# Eeprom.net
KiCad netlist of a schematic drawn in Altium Designer
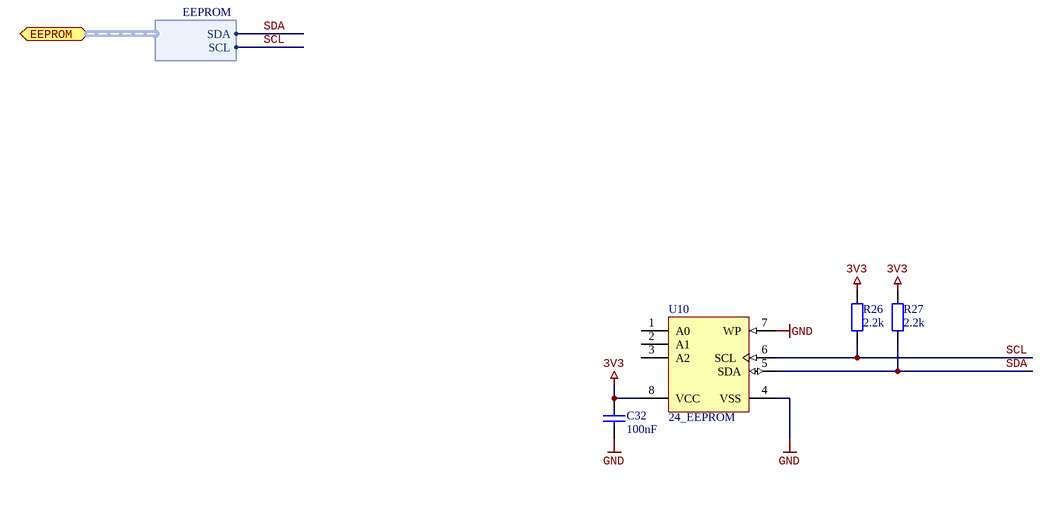
[diagram p0: Eeprom.SchDoc]

(export (version "E")
  (design (tool "Eeschema 10.0.6"))
  (components
    (comp (ref "C32")
      (value "100nF")
      (footprint "CAPC1608N")
      (description "Capacitor")
      (libsource (lib "Discrete") (part "Capacitor"))
    )
    (comp (ref "R26")
      (value "2.2k")
      (footprint "RESC1608N")
      (description "Resistor")
      (fields (field (name "POWER") "0W") (field (name "TOLERANCE") "5%"))
      (libsource (lib "Discrete") (part "Resistor"))
    )
    (comp (ref "R27")
      (value "2.2k")
      (footprint "RESC1608N")
      (description "Resistor")
      (fields (field (name "POWER") "0W") (field (name "TOLERANCE") "5%"))
      (libsource (lib "Discrete") (part "Resistor"))
    )
    (comp (ref "U10")
      (value "24_EEPROM")
      (footprint "SO-8_L")
      (description "16Kbit, 400kHz, 2.5V, I2C Serial EEPROM, 8-Pin SOIC 150mil, Extended Temperature")
      (libsource (lib "my_various_devices") (part "24_EEPROM"))
    )
  )
  (nets
    (net (code "2") (name "/SCL") (class "Default")
      (node (ref "R26") (pin "2") (pinfunction "2_2") (pintype "passive"))
      (node (ref "U10") (pin "6") (pinfunction "SCL_6") (pintype "input"))
    )
    (net (code "3") (name "/SDA") (class "Default")
      (node (ref "R27") (pin "2") (pinfunction "2_2") (pintype "passive"))
      (node (ref "U10") (pin "5") (pinfunction "SDA_5") (pintype "bidirectional"))
    )
    (net (code "5") (name "3V3") (class "Default")
      (node (ref "C32") (pin "1") (pinfunction "1_1") (pintype "passive"))
      (node (ref "R26") (pin "1") (pinfunction "1_1") (pintype "passive"))
      (node (ref "R27") (pin "1") (pinfunction "1_1") (pintype "passive"))
      (node (ref "U10") (pin "8") (pinfunction "VCC_8") (pintype "power_in"))
    )
    (net (code "6") (name "GND") (class "Default")
      (node (ref "C32") (pin "2") (pinfunction "2_2") (pintype "passive"))
      (node (ref "U10") (pin "4") (pinfunction "VSS_4") (pintype "power_in"))
      (node (ref "U10") (pin "7") (pinfunction "WP_7") (pintype "input"))
    )
    (net (code "7") (name "unconnected-(U10-A0-Pad1)") (class "Default")
      (node (ref "U10") (pin "1") (pinfunction "A0_1") (pintype "passive"))
    )
    (net (code "8") (name "unconnected-(U10-A1-Pad2)") (class "Default")
      (node (ref "U10") (pin "2") (pinfunction "A1_2") (pintype "passive"))
    )
    (net (code "9") (name "unconnected-(U10-A2-Pad3)") (class "Default")
      (node (ref "U10") (pin "3") (pinfunction "A2_3") (pintype "passive"))
    )
  )
)
